# variable_supply_module_v3.net
KiCad netlist of a schematic drawn in EAGLE
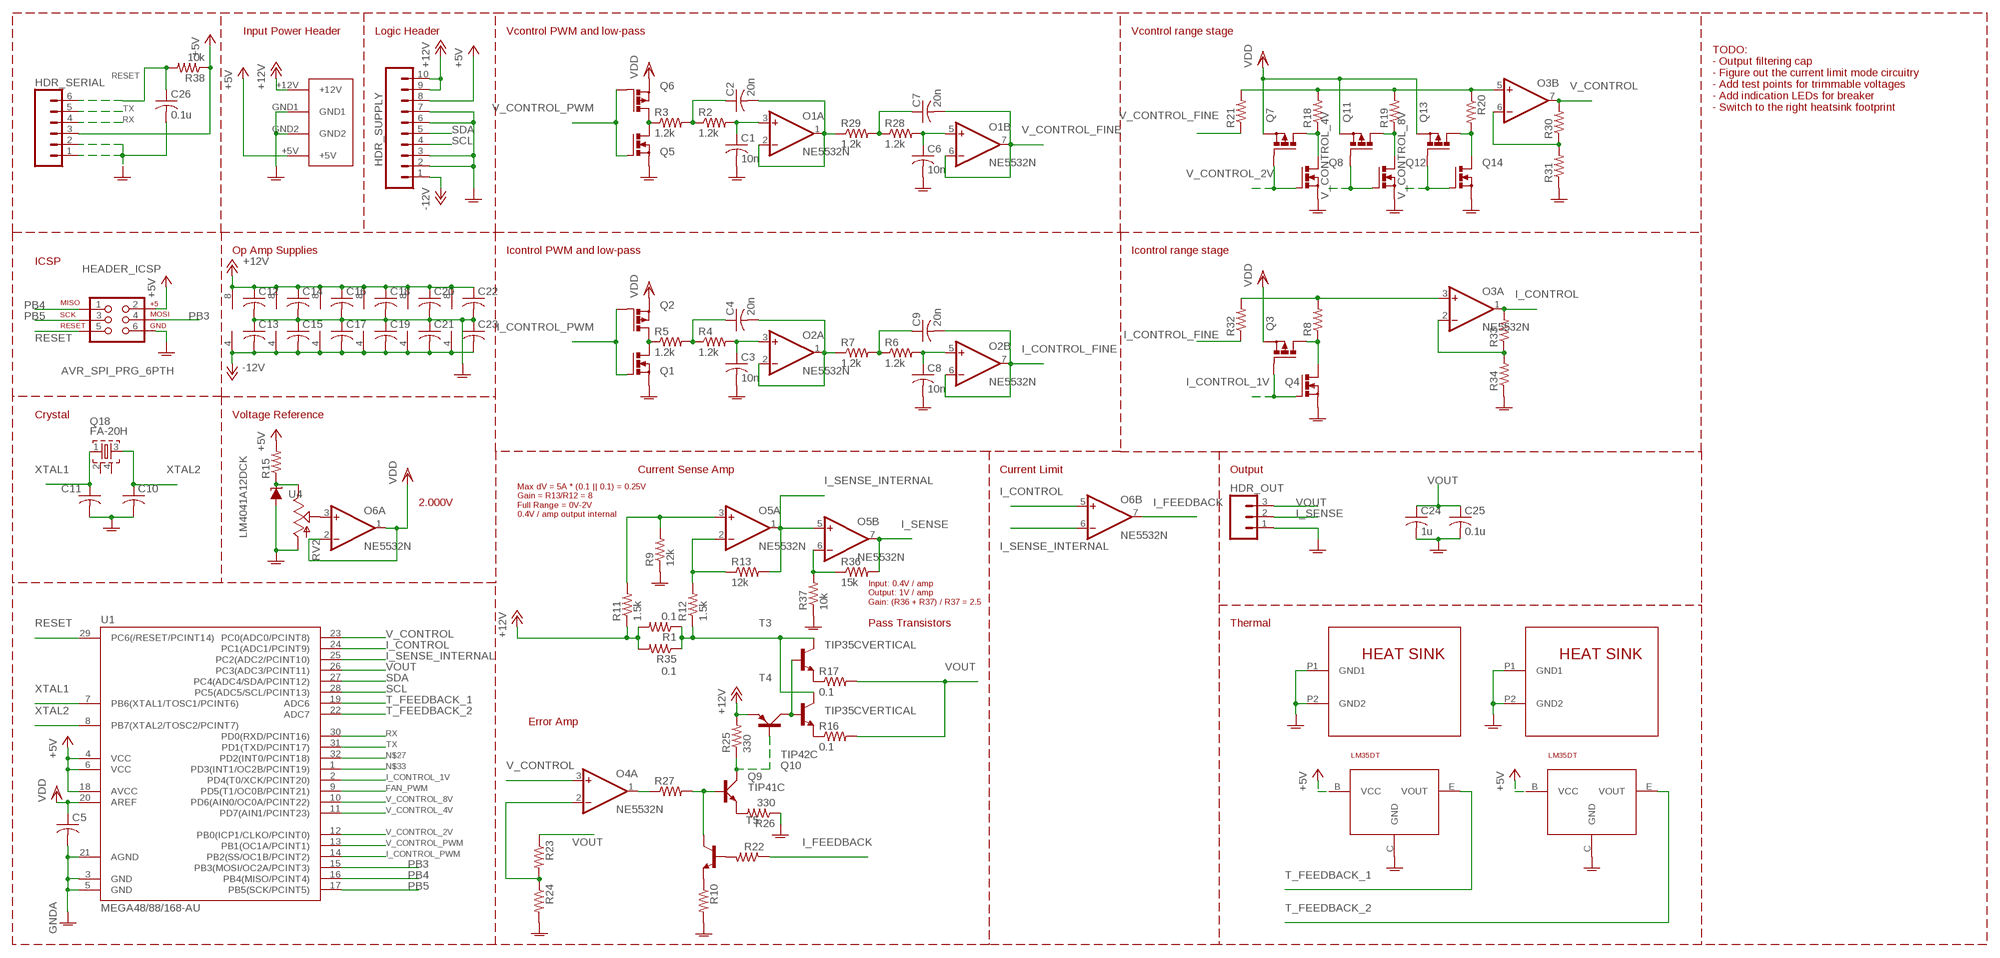
[diagram p0: schematic, sheet 1]

(export (version "E")
  (design (tool "Eeschema 10.0.6"))
  (components
    (comp (ref "C1")
      (value "10n")
      (footprint "eagle-import:C0805")
      (libsource (lib "eagle-import") (part "C-USC0805"))
    )
    (comp (ref "C2")
      (value "20n")
      (footprint "eagle-import:C0805")
      (libsource (lib "eagle-import") (part "C-USC0805"))
    )
    (comp (ref "C3")
      (value "10n")
      (footprint "eagle-import:C0805")
      (libsource (lib "eagle-import") (part "C-USC0805"))
    )
    (comp (ref "C4")
      (value "20n")
      (footprint "eagle-import:C0805")
      (libsource (lib "eagle-import") (part "C-USC0805"))
    )
    (comp (ref "C5")
      (value "C-USC0805")
      (footprint "eagle-import:C0805")
      (libsource (lib "eagle-import") (part "C-USC0805"))
    )
    (comp (ref "C6")
      (value "10n")
      (footprint "eagle-import:C0805")
      (libsource (lib "eagle-import") (part "C-USC0805"))
    )
    (comp (ref "C7")
      (value "20n")
      (footprint "eagle-import:C0805")
      (libsource (lib "eagle-import") (part "C-USC0805"))
    )
    (comp (ref "C8")
      (value "10n")
      (footprint "eagle-import:C0805")
      (libsource (lib "eagle-import") (part "C-USC0805"))
    )
    (comp (ref "C9")
      (value "20n")
      (footprint "eagle-import:C0805")
      (libsource (lib "eagle-import") (part "C-USC0805"))
    )
    (comp (ref "C10")
      (value "C-USC0805")
      (footprint "eagle-import:C0805")
      (libsource (lib "eagle-import") (part "C-USC0805"))
    )
    (comp (ref "C11")
      (value "C-USC0805")
      (footprint "eagle-import:C0805")
      (libsource (lib "eagle-import") (part "C-USC0805"))
    )
    (comp (ref "C12")
      (value "C-USC0805")
      (footprint "eagle-import:C0805")
      (libsource (lib "eagle-import") (part "C-USC0805"))
    )
    (comp (ref "C13")
      (value "C-USC0805")
      (footprint "eagle-import:C0805")
      (libsource (lib "eagle-import") (part "C-USC0805"))
    )
    (comp (ref "C14")
      (value "C-USC0805")
      (footprint "eagle-import:C0805")
      (libsource (lib "eagle-import") (part "C-USC0805"))
    )
    (comp (ref "C15")
      (value "C-USC0805")
      (footprint "eagle-import:C0805")
      (libsource (lib "eagle-import") (part "C-USC0805"))
    )
    (comp (ref "C16")
      (value "C-USC0805")
      (footprint "eagle-import:C0805")
      (libsource (lib "eagle-import") (part "C-USC0805"))
    )
    (comp (ref "C17")
      (value "C-USC0805")
      (footprint "eagle-import:C0805")
      (libsource (lib "eagle-import") (part "C-USC0805"))
    )
    (comp (ref "C18")
      (value "C-USC0805")
      (footprint "eagle-import:C0805")
      (libsource (lib "eagle-import") (part "C-USC0805"))
    )
    (comp (ref "C19")
      (value "C-USC0805")
      (footprint "eagle-import:C0805")
      (libsource (lib "eagle-import") (part "C-USC0805"))
    )
    (comp (ref "C20")
      (value "C-USC0805")
      (footprint "eagle-import:C0805")
      (libsource (lib "eagle-import") (part "C-USC0805"))
    )
    (comp (ref "C21")
      (value "C-USC0805")
      (footprint "eagle-import:C0805")
      (libsource (lib "eagle-import") (part "C-USC0805"))
    )
    (comp (ref "C22")
      (value "C-USC0805")
      (footprint "eagle-import:C0805")
      (libsource (lib "eagle-import") (part "C-USC0805"))
    )
    (comp (ref "C23")
      (value "C-USC0805")
      (footprint "eagle-import:C0805")
      (libsource (lib "eagle-import") (part "C-USC0805"))
    )
    (comp (ref "C24")
      (value "1u")
      (footprint "eagle-import:C1206")
      (libsource (lib "eagle-import") (part "C-USC1206"))
    )
    (comp (ref "C25")
      (value "0.1u")
      (footprint "eagle-import:C1206")
      (libsource (lib "eagle-import") (part "C-USC1206"))
    )
    (comp (ref "C26")
      (value "0.1u")
      (footprint "eagle-import:C0805")
      (libsource (lib "eagle-import") (part "C-USC0805"))
    )
    (comp (ref "HDR_OUT")
      (value "M03")
      (footprint "eagle-import:03P")
      (libsource (lib "eagle-import") (part "M03"))
    )
    (comp (ref "HDR_SERIAL")
      (value "M06LONGPADS")
      (footprint "eagle-import:1X06_LONGPADS")
      (libsource (lib "eagle-import") (part "M06LONGPADS"))
    )
    (comp (ref "HDR_SUPPLY")
      (value "M10")
      (footprint "eagle-import:10P")
      (libsource (lib "eagle-import") (part "M10"))
    )
    (comp (ref "HEADER_ICSP")
      (value "AVR_SPI_PRG_6PTH")
      (footprint "eagle-import:2X3")
      (libsource (lib "eagle-import") (part "AVR_SPI_PRG_6PTH"))
    )
    (comp (ref "O1")
      (value "NE5532N")
      (footprint "eagle-import:DIL08")
      (libsource (lib "eagle-import") (part "NE5532N"))
    )
    (comp (ref "O2")
      (value "NE5532N")
      (footprint "eagle-import:DIL08")
      (libsource (lib "eagle-import") (part "NE5532N"))
    )
    (comp (ref "O3")
      (value "NE5532N")
      (footprint "eagle-import:DIL08")
      (libsource (lib "eagle-import") (part "NE5532N"))
    )
    (comp (ref "O4")
      (value "NE5532N")
      (footprint "eagle-import:DIL08")
      (libsource (lib "eagle-import") (part "NE5532N"))
    )
    (comp (ref "O5")
      (value "NE5532N")
      (footprint "eagle-import:DIL08")
      (libsource (lib "eagle-import") (part "NE5532N"))
    )
    (comp (ref "O6")
      (value "NE5532N")
      (footprint "eagle-import:DIL08")
      (libsource (lib "eagle-import") (part "NE5532N"))
    )
    (comp (ref "Q1")
      (value "PMOSFET_NSOT23-GSD")
      (footprint "eagle-import:SOT23")
      (libsource (lib "eagle-import") (part "PMOSFET_NSOT23-GSD"))
    )
    (comp (ref "Q2")
      (value "PMOSFET_PSOT-23GSD")
      (footprint "eagle-import:SOT23")
      (libsource (lib "eagle-import") (part "PMOSFET_PSOT-23GSD"))
    )
    (comp (ref "Q3")
      (value "PMOSFET_PSOT-23GSD")
      (footprint "eagle-import:SOT23")
      (libsource (lib "eagle-import") (part "PMOSFET_PSOT-23GSD"))
    )
    (comp (ref "Q4")
      (value "PMOSFET_NSOT23-GSD")
      (footprint "eagle-import:SOT23")
      (libsource (lib "eagle-import") (part "PMOSFET_NSOT23-GSD"))
    )
    (comp (ref "Q5")
      (value "PMOSFET_NSOT23-GSD")
      (footprint "eagle-import:SOT23")
      (libsource (lib "eagle-import") (part "PMOSFET_NSOT23-GSD"))
    )
    (comp (ref "Q6")
      (value "PMOSFET_PSOT-23GSD")
      (footprint "eagle-import:SOT23")
      (libsource (lib "eagle-import") (part "PMOSFET_PSOT-23GSD"))
    )
    (comp (ref "Q7")
      (value "PMOSFET_PSOT-23GSD")
      (footprint "eagle-import:SOT23")
      (libsource (lib "eagle-import") (part "PMOSFET_PSOT-23GSD"))
    )
    (comp (ref "Q8")
      (value "PMOSFET_NSOT23-GSD")
      (footprint "eagle-import:SOT23")
      (libsource (lib "eagle-import") (part "PMOSFET_NSOT23-GSD"))
    )
    (comp (ref "Q9")
      (value "TIP41C")
      (footprint "eagle-import:TO220AV")
      (libsource (lib "eagle-import") (part "TIP41C"))
    )
    (comp (ref "Q10")
      (value "TIP42C")
      (footprint "eagle-import:TO220AV")
      (libsource (lib "eagle-import") (part "TIP42C"))
    )
    (comp (ref "Q11")
      (value "PMOSFET_PSOT-23GSD")
      (footprint "eagle-import:SOT23")
      (libsource (lib "eagle-import") (part "PMOSFET_PSOT-23GSD"))
    )
    (comp (ref "Q12")
      (value "PMOSFET_NSOT23-GSD")
      (footprint "eagle-import:SOT23")
      (libsource (lib "eagle-import") (part "PMOSFET_NSOT23-GSD"))
    )
    (comp (ref "Q13")
      (value "PMOSFET_PSOT-23GSD")
      (footprint "eagle-import:SOT23")
      (libsource (lib "eagle-import") (part "PMOSFET_PSOT-23GSD"))
    )
    (comp (ref "Q14")
      (value "PMOSFET_NSOT23-GSD")
      (footprint "eagle-import:SOT23")
      (libsource (lib "eagle-import") (part "PMOSFET_NSOT23-GSD"))
    )
    (comp (ref "Q18")
      (value "FA-20H")
      (footprint "eagle-import:FA-20H")
      (libsource (lib "eagle-import") (part "FA-20H"))
    )
    (comp (ref "R1")
      (value "0.1")
      (footprint "eagle-import:R2010")
      (libsource (lib "eagle-import") (part "R-US_R2010"))
    )
    (comp (ref "R2")
      (value "1.2k")
      (footprint "eagle-import:M0805")
      (libsource (lib "eagle-import") (part "R-US_M0805"))
    )
    (comp (ref "R3")
      (value "1.2k")
      (footprint "eagle-import:M0805")
      (libsource (lib "eagle-import") (part "R-US_M0805"))
    )
    (comp (ref "R4")
      (value "1.2k")
      (footprint "eagle-import:M0805")
      (libsource (lib "eagle-import") (part "R-US_M0805"))
    )
    (comp (ref "R5")
      (value "1.2k")
      (footprint "eagle-import:M0805")
      (libsource (lib "eagle-import") (part "R-US_M0805"))
    )
    (comp (ref "R6")
      (value "1.2k")
      (footprint "eagle-import:M0805")
      (libsource (lib "eagle-import") (part "R-US_M0805"))
    )
    (comp (ref "R7")
      (value "1.2k")
      (footprint "eagle-import:M0805")
      (libsource (lib "eagle-import") (part "R-US_M0805"))
    )
    (comp (ref "R8")
      (value "R-US_M0805")
      (footprint "eagle-import:M0805")
      (libsource (lib "eagle-import") (part "R-US_M0805"))
    )
    (comp (ref "R9")
      (value "12k")
      (footprint "eagle-import:M0805")
      (libsource (lib "eagle-import") (part "R-US_M0805"))
    )
    (comp (ref "R10")
      (value "R-US_M0805")
      (footprint "eagle-import:M0805")
      (libsource (lib "eagle-import") (part "R-US_M0805"))
    )
    (comp (ref "R11")
      (value "1.5k")
      (footprint "eagle-import:M0805")
      (libsource (lib "eagle-import") (part "R-US_M0805"))
    )
    (comp (ref "R12")
      (value "1.5k")
      (footprint "eagle-import:M0805")
      (libsource (lib "eagle-import") (part "R-US_M0805"))
    )
    (comp (ref "R13")
      (value "12k")
      (footprint "eagle-import:M0805")
      (libsource (lib "eagle-import") (part "R-US_M0805"))
    )
    (comp (ref "R15")
      (value "R-US_M0805")
      (footprint "eagle-import:M0805")
      (libsource (lib "eagle-import") (part "R-US_M0805"))
    )
    (comp (ref "R16")
      (value "0.1")
      (footprint "eagle-import:R2010")
      (libsource (lib "eagle-import") (part "R-US_R2010"))
    )
    (comp (ref "R17")
      (value "0.1")
      (footprint "eagle-import:R2010")
      (libsource (lib "eagle-import") (part "R-US_R2010"))
    )
    (comp (ref "R18")
      (value "R-US_M0805")
      (footprint "eagle-import:M0805")
      (libsource (lib "eagle-import") (part "R-US_M0805"))
    )
    (comp (ref "R19")
      (value "R-US_M0805")
      (footprint "eagle-import:M0805")
      (libsource (lib "eagle-import") (part "R-US_M0805"))
    )
    (comp (ref "R20")
      (value "R-US_M0805")
      (footprint "eagle-import:M0805")
      (libsource (lib "eagle-import") (part "R-US_M0805"))
    )
    (comp (ref "R21")
      (value "R-US_M0805")
      (footprint "eagle-import:M0805")
      (libsource (lib "eagle-import") (part "R-US_M0805"))
    )
    (comp (ref "R22")
      (value "R-US_M0805")
      (footprint "eagle-import:M0805")
      (libsource (lib "eagle-import") (part "R-US_M0805"))
    )
    (comp (ref "R23")
      (value "R-US_M0805")
      (footprint "eagle-import:M0805")
      (libsource (lib "eagle-import") (part "R-US_M0805"))
    )
    (comp (ref "R24")
      (value "R-US_M0805")
      (footprint "eagle-import:M0805")
      (libsource (lib "eagle-import") (part "R-US_M0805"))
    )
    (comp (ref "R25")
      (value "330")
      (footprint "eagle-import:M0805")
      (libsource (lib "eagle-import") (part "R-US_M0805"))
    )
    (comp (ref "R26")
      (value "330")
      (footprint "eagle-import:M0805")
      (libsource (lib "eagle-import") (part "R-US_M0805"))
    )
    (comp (ref "R27")
      (value "R-US_M0805")
      (footprint "eagle-import:M0805")
      (libsource (lib "eagle-import") (part "R-US_M0805"))
    )
    (comp (ref "R28")
      (value "1.2k")
      (footprint "eagle-import:M0805")
      (libsource (lib "eagle-import") (part "R-US_M0805"))
    )
    (comp (ref "R29")
      (value "1.2k")
      (footprint "eagle-import:M0805")
      (libsource (lib "eagle-import") (part "R-US_M0805"))
    )
    (comp (ref "R30")
      (value "R-US_M0805")
      (footprint "eagle-import:M0805")
      (libsource (lib "eagle-import") (part "R-US_M0805"))
    )
    (comp (ref "R31")
      (value "R-US_M0805")
      (footprint "eagle-import:M0805")
      (libsource (lib "eagle-import") (part "R-US_M0805"))
    )
    (comp (ref "R32")
      (value "R-US_M0805")
      (footprint "eagle-import:M0805")
      (libsource (lib "eagle-import") (part "R-US_M0805"))
    )
    (comp (ref "R33")
      (value "R-US_M0805")
      (footprint "eagle-import:M0805")
      (libsource (lib "eagle-import") (part "R-US_M0805"))
    )
    (comp (ref "R34")
      (value "R-US_M0805")
      (footprint "eagle-import:M0805")
      (libsource (lib "eagle-import") (part "R-US_M0805"))
    )
    (comp (ref "R35")
      (value "0.1")
      (footprint "eagle-import:R2010")
      (libsource (lib "eagle-import") (part "R-US_R2010"))
    )
    (comp (ref "R36")
      (value "15k")
      (footprint "eagle-import:M0805")
      (libsource (lib "eagle-import") (part "R-US_M0805"))
    )
    (comp (ref "R37")
      (value "10k")
      (footprint "eagle-import:M0805")
      (libsource (lib "eagle-import") (part "R-US_M0805"))
    )
    (comp (ref "R38")
      (value "10k")
      (footprint "eagle-import:M0805")
      (libsource (lib "eagle-import") (part "R-US_M0805"))
    )
    (comp (ref "RV2")
      (value "POTTRIM")
      (footprint "eagle-import:TRIM_POT")
      (libsource (lib "eagle-import") (part "POTTRIM"))
    )
    (comp (ref "T3")
      (value "TIP35CVERTICAL")
      (footprint "eagle-import:TO247")
      (libsource (lib "eagle-import") (part "TIP35CVERTICAL"))
    )
    (comp (ref "T4")
      (value "TIP35CVERTICAL")
      (footprint "eagle-import:TO247")
      (libsource (lib "eagle-import") (part "TIP35CVERTICAL"))
    )
    (comp (ref "T5")
      (value "MMBT2222ALT1-NPN-SOT23-BEC")
      (footprint "eagle-import:SOT23-BEC")
      (libsource (lib "eagle-import") (part "-NPN-SOT23-BECMMBT2222ALT1"))
    )
    (comp (ref "U$1")
      (value "MOLEX-8981")
      (footprint "eagle-import:MOLEX-8981-MALE")
      (libsource (lib "eagle-import") (part "MOLEX-8981"))
    )
    (comp (ref "U$2")
      (value "FA-T220-X")
      (footprint "eagle-import:FA-T220-X")
      (libsource (lib "eagle-import") (part "FA-T220-X"))
    )
    (comp (ref "U$3")
      (value "FA-T220-X")
      (footprint "eagle-import:FA-T220-X")
      (libsource (lib "eagle-import") (part "FA-T220-X"))
    )
    (comp (ref "U1")
      (value "MEGA48/88/168-AU")
      (footprint "eagle-import:TQFP32-08")
      (libsource (lib "eagle-import") (part "MEGA48/88/168-AU"))
    )
    (comp (ref "U2")
      (value "LM35DT")
      (footprint "eagle-import:TO220AV")
      (libsource (lib "eagle-import") (part "LM35DT"))
    )
    (comp (ref "U3")
      (value "LM35DT")
      (footprint "eagle-import:TO220AV")
      (libsource (lib "eagle-import") (part "LM35DT"))
    )
    (comp (ref "U4")
      (value "LM4041A12DCK")
      (footprint "eagle-import:DCK_R-PDSO-G5")
      (fields (field (name "MPN") "LM4041A12IDCKR"))
      (libsource (lib "eagle-import") (part "LM4041DCKA12"))
    )
  )
  (nets
    (net (code "1") (name "+5V") (class "Default")
      (node (ref "HDR_SERIAL") (pin "3") (pinfunction "3_3") (pintype "passive"))
      (node (ref "HDR_SUPPLY") (pin "8") (pinfunction "8_8") (pintype "passive"))
      (node (ref "HEADER_ICSP") (pin "2") (pinfunction "2_2") (pintype "passive"))
      (node (ref "R15") (pin "2") (pinfunction "2_2") (pintype "passive"))
      (node (ref "R38") (pin "1") (pinfunction "1_1") (pintype "passive"))
      (node (ref "U$1") (pin "+5V") (pinfunction "+5V_+5V") (pintype "bidirectional"))
      (node (ref "U1") (pin "18") (pinfunction "AVCC_18") (pintype "passive"))
      (node (ref "U1") (pin "4") (pinfunction "VCC_4") (pintype "power_in"))
      (node (ref "U1") (pin "6") (pinfunction "VCC_6") (pintype "power_in"))
      (node (ref "U2") (pin "B") (pinfunction "VCC_B") (pintype "bidirectional"))
      (node (ref "U3") (pin "B") (pinfunction "VCC_B") (pintype "bidirectional"))
    )
    (net (code "2") (name "+12V") (class "Default")
      (node (ref "C12") (pin "1") (pinfunction "1_1") (pintype "passive"))
      (node (ref "C14") (pin "1") (pinfunction "1_1") (pintype "passive"))
      (node (ref "C16") (pin "1") (pinfunction "1_1") (pintype "passive"))
      (node (ref "C18") (pin "1") (pinfunction "1_1") (pintype "passive"))
      (node (ref "C20") (pin "1") (pinfunction "1_1") (pintype "passive"))
      (node (ref "C22") (pin "1") (pinfunction "1_1") (pintype "passive"))
      (node (ref "HDR_SUPPLY") (pin "10") (pinfunction "10_10") (pintype "passive"))
      (node (ref "HDR_SUPPLY") (pin "9") (pinfunction "9_9") (pintype "passive"))
      (node (ref "O1") (pin "8") (pinfunction "V+_8") (pintype "power_in"))
      (node (ref "O2") (pin "8") (pinfunction "V+_8") (pintype "power_in"))
      (node (ref "O3") (pin "8") (pinfunction "V+_8") (pintype "power_in"))
      (node (ref "O4") (pin "8") (pinfunction "V+_8") (pintype "power_in"))
      (node (ref "O5") (pin "8") (pinfunction "V+_8") (pintype "power_in"))
      (node (ref "O6") (pin "8") (pinfunction "V+_8") (pintype "power_in"))
      (node (ref "Q10") (pin "E") (pinfunction "E_E") (pintype "passive"))
      (node (ref "R1") (pin "2") (pinfunction "2_2") (pintype "passive"))
      (node (ref "R11") (pin "1") (pinfunction "1_1") (pintype "passive"))
      (node (ref "R25") (pin "2") (pinfunction "2_2") (pintype "passive"))
      (node (ref "R35") (pin "2") (pinfunction "2_2") (pintype "passive"))
      (node (ref "U$1") (pin "+12V") (pinfunction "+12V_+12V") (pintype "bidirectional"))
    )
    (net (code "3") (name "-12V") (class "Default")
      (node (ref "C13") (pin "2") (pinfunction "2_2") (pintype "passive"))
      (node (ref "C15") (pin "2") (pinfunction "2_2") (pintype "passive"))
      (node (ref "C17") (pin "2") (pinfunction "2_2") (pintype "passive"))
      (node (ref "C19") (pin "2") (pinfunction "2_2") (pintype "passive"))
      (node (ref "C21") (pin "2") (pinfunction "2_2") (pintype "passive"))
      (node (ref "C23") (pin "2") (pinfunction "2_2") (pintype "passive"))
      (node (ref "HDR_SUPPLY") (pin "1") (pinfunction "1_1") (pintype "passive"))
      (node (ref "O1") (pin "4") (pinfunction "V-_4") (pintype "power_in"))
      (node (ref "O2") (pin "4") (pinfunction "V-_4") (pintype "power_in"))
      (node (ref "O3") (pin "4") (pinfunction "V-_4") (pintype "power_in"))
      (node (ref "O4") (pin "4") (pinfunction "V-_4") (pintype "power_in"))
      (node (ref "O5") (pin "4") (pinfunction "V-_4") (pintype "power_in"))
      (node (ref "O6") (pin "4") (pinfunction "V-_4") (pintype "power_in"))
    )
    (net (code "4") (name "/FAN_PWM") (class "Default")
      (node (ref "U1") (pin "9") (pinfunction "PD5(T1/OC0B/PCINT21)_9") (pintype "bidirectional"))
    )
    (net (code "5") (name "/I_CONTROL") (class "Default")
      (node (ref "O3") (pin "1") (pinfunction "OUT_1") (pintype "output"))
      (node (ref "O6") (pin "5") (pinfunction "+IN_5") (pintype "input"))
      (node (ref "R33") (pin "2") (pinfunction "2_2") (pintype "passive"))
      (node (ref "U1") (pin "24") (pinfunction "PC1(ADC1/PCINT9)_24") (pintype "bidirectional"))
    )
    (net (code "6") (name "/I_CONTROL_1V") (class "Default")
      (node (ref "Q3") (pin "1") (pinfunction "G_1") (pintype "passive"))
      (node (ref "Q4") (pin "1") (pinfunction "G_1") (pintype "passive"))
      (node (ref "U1") (pin "2") (pinfunction "PD4(T0/XCK/PCINT20)_2") (pintype "bidirectional"))
    )
    (net (code "7") (name "/I_CONTROL_FINE") (class "Default")
      (node (ref "C9") (pin "2") (pinfunction "2_2") (pintype "passive"))
      (node (ref "O2") (pin "6") (pinfunction "-IN_6") (pintype "input"))
      (node (ref "O2") (pin "7") (pinfunction "OUT_7") (pintype "output"))
      (node (ref "R32") (pin "1") (pinfunction "1_1") (pintype "passive"))
    )
    (net (code "8") (name "/I_CONTROL_PWM") (class "Default")
      (node (ref "Q1") (pin "1") (pinfunction "G_1") (pintype "passive"))
      (node (ref "Q2") (pin "1") (pinfunction "G_1") (pintype "passive"))
      (node (ref "U1") (pin "14") (pinfunction "PB2(SS/OC1B/PCINT2)_14") (pintype "bidirectional"))
    )
    (net (code "9") (name "/I_FEEDBACK") (class "Default")
      (node (ref "O6") (pin "7") (pinfunction "OUT_7") (pintype "output"))
      (node (ref "R22") (pin "1") (pinfunction "1_1") (pintype "passive"))
    )
    (net (code "10") (name "/I_SENSE") (class "Default")
      (node (ref "HDR_OUT") (pin "2") (pinfunction "2_2") (pintype "passive"))
      (node (ref "O5") (pin "7") (pinfunction "OUT_7") (pintype "output"))
      (node (ref "R36") (pin "2") (pinfunction "2_2") (pintype "passive"))
    )
    (net (code "11") (name "/I_SENSE_INTERNAL") (class "Default")
      (node (ref "O5") (pin "1") (pinfunction "OUT_1") (pintype "output"))
      (node (ref "O5") (pin "5") (pinfunction "+IN_5") (pintype "input"))
      (node (ref "O6") (pin "6") (pinfunction "-IN_6") (pintype "input"))
      (node (ref "R13") (pin "2") (pinfunction "2_2") (pintype "passive"))
      (node (ref "U1") (pin "25") (pinfunction "PC2(ADC2/PCINT10)_25") (pintype "bidirectional"))
    )
    (net (code "12") (name "/N$27") (class "Default")
      (node (ref "U1") (pin "32") (pinfunction "PD2(INT0/PCINT18)_32") (pintype "bidirectional"))
    )
    (net (code "13") (name "/N$33") (class "Default")
      (node (ref "U1") (pin "1") (pinfunction "PD3(INT1/OC2B/PCINT19)_1") (pintype "bidirectional"))
    )
    (net (code "14") (name "/PB3") (class "Default")
      (node (ref "HEADER_ICSP") (pin "4") (pinfunction "4_4") (pintype "passive"))
      (node (ref "U1") (pin "15") (pinfunction "PB3(MOSI/OC2A/PCINT3)_15") (pintype "bidirectional"))
    )
    (net (code "15") (name "/PB4") (class "Default")
      (node (ref "HEADER_ICSP") (pin "1") (pinfunction "1_1") (pintype "passive"))
      (node (ref "U1") (pin "16") (pinfunction "PB4(MISO/PCINT4)_16") (pintype "bidirectional"))
    )
    (net (code "16") (name "/PB5") (class "Default")
      (node (ref "HEADER_ICSP") (pin "3") (pinfunction "3_3") (pintype "passive"))
      (node (ref "U1") (pin "17") (pinfunction "PB5(SCK/PCINT5)_17") (pintype "bidirectional"))
    )
    (net (code "17") (name "/RESET") (class "Default")
      (node (ref "C26") (pin "1") (pinfunction "1_1") (pintype "passive"))
      (node (ref "HDR_SERIAL") (pin "6") (pinfunction "6_6") (pintype "passive"))
      (node (ref "HEADER_ICSP") (pin "5") (pinfunction "5_5") (pintype "passive"))
      (node (ref "R38") (pin "2") (pinfunction "2_2") (pintype "passive"))
      (node (ref "U1") (pin "29") (pinfunction "PC6(/RESET/PCINT14)_29") (pintype "bidirectional"))
    )
    (net (code "18") (name "/RX") (class "Default")
      (node (ref "HDR_SERIAL") (pin "4") (pinfunction "4_4") (pintype "passive"))
      (node (ref "U1") (pin "30") (pinfunction "PD0(RXD/PCINT16)_30") (pintype "bidirectional"))
    )
    (net (code "19") (name "/SCL") (class "Default")
      (node (ref "HDR_SUPPLY") (pin "4") (pinfunction "4_4") (pintype "passive"))
      (node (ref "U1") (pin "28") (pinfunction "PC5(ADC5/SCL/PCINT13)_28") (pintype "bidirectional"))
    )
    (net (code "20") (name "/SDA") (class "Default")
      (node (ref "HDR_SUPPLY") (pin "5") (pinfunction "5_5") (pintype "passive"))
      (node (ref "U1") (pin "27") (pinfunction "PC4(ADC4/SDA/PCINT12)_27") (pintype "bidirectional"))
    )
    (net (code "21") (name "/TX") (class "Default")
      (node (ref "HDR_SERIAL") (pin "5") (pinfunction "5_5") (pintype "passive"))
      (node (ref "U1") (pin "31") (pinfunction "PD1(TXD/PCINT17)_31") (pintype "bidirectional"))
    )
    (net (code "22") (name "/T_FEEDBACK_1") (class "Default")
      (node (ref "U1") (pin "19") (pinfunction "ADC6_19") (pintype "passive"))
      (node (ref "U2") (pin "E") (pinfunction "VOUT_E") (pintype "bidirectional"))
    )
    (net (code "23") (name "/T_FEEDBACK_2") (class "Default")
      (node (ref "U1") (pin "22") (pinfunction "ADC7_22") (pintype "passive"))
      (node (ref "U3") (pin "E") (pinfunction "VOUT_E") (pintype "bidirectional"))
    )
    (net (code "24") (name "/VOUT") (class "Default")
      (node (ref "C24") (pin "1") (pinfunction "1_1") (pintype "passive"))
      (node (ref "C25") (pin "1") (pinfunction "1_1") (pintype "passive"))
      (node (ref "HDR_OUT") (pin "3") (pinfunction "3_3") (pintype "passive"))
      (node (ref "R16") (pin "2") (pinfunction "2_2") (pintype "passive"))
      (node (ref "R17") (pin "2") (pinfunction "2_2") (pintype "passive"))
      (node (ref "R23") (pin "1") (pinfunction "1_1") (pintype "passive"))
      (node (ref "U1") (pin "26") (pinfunction "PC3(ADC3/PCINT11)_26") (pintype "bidirectional"))
    )
    (net (code "25") (name "/V_CONTROL") (class "Default")
      (node (ref "O3") (pin "7") (pinfunction "OUT_7") (pintype "output"))
      (node (ref "O4") (pin "3") (pinfunction "+IN_3") (pintype "input"))
      (node (ref "R30") (pin "2") (pinfunction "2_2") (pintype "passive"))
      (node (ref "U1") (pin "23") (pinfunction "PC0(ADC0/PCINT8)_23") (pintype "bidirectional"))
    )
    (net (code "26") (name "/V_CONTROL_2V") (class "Default")
      (node (ref "Q7") (pin "1") (pinfunction "G_1") (pintype "passive"))
      (node (ref "Q8") (pin "1") (pinfunction "G_1") (pintype "passive"))
      (node (ref "U1") (pin "12") (pinfunction "PB0(ICP1/CLKO/PCINT0)_12") (pintype "bidirectional"))
    )
    (net (code "27") (name "/V_CONTROL_4V") (class "Default")
      (node (ref "Q11") (pin "1") (pinfunction "G_1") (pintype "passive"))
      (node (ref "Q12") (pin "1") (pinfunction "G_1") (pintype "passive"))
      (node (ref "U1") (pin "11") (pinfunction "PD7(AIN1/PCINT23)_11") (pintype "bidirectional"))
    )
    (net (code "28") (name "/V_CONTROL_8V") (class "Default")
      (node (ref "Q13") (pin "1") (pinfunction "G_1") (pintype "passive"))
      (node (ref "Q14") (pin "1") (pinfunction "G_1") (pintype "passive"))
      (node (ref "U1") (pin "10") (pinfunction "PD6(AIN0/OC0A/PCINT22)_10") (pintype "bidirectional"))
    )
    (net (code "29") (name "/V_CONTROL_FINE") (class "Default")
      (node (ref "C7") (pin "2") (pinfunction "2_2") (pintype "passive"))
      (node (ref "O1") (pin "6") (pinfunction "-IN_6") (pintype "input"))
      (node (ref "O1") (pin "7") (pinfunction "OUT_7") (pintype "output"))
      (node (ref "R21") (pin "1") (pinfunction "1_1") (pintype "passive"))
    )
    (net (code "30") (name "/V_CONTROL_PWM") (class "Default")
      (node (ref "Q5") (pin "1") (pinfunction "G_1") (pintype "passive"))
      (node (ref "Q6") (pin "1") (pinfunction "G_1") (pintype "passive"))
      (node (ref "U1") (pin "13") (pinfunction "PB1(OC1A/PCINT1)_13") (pintype "bidirectional"))
    )
    (net (code "31") (name "/XTAL1") (class "Default")
      (node (ref "C11") (pin "1") (pinfunction "1_1") (pintype "passive"))
      (node (ref "Q18") (pin "1") (pinfunction "1_1") (pintype "passive"))
      (node (ref "U1") (pin "7") (pinfunction "PB6(XTAL1/TOSC1/PCINT6)_7") (pintype "bidirectional"))
    )
    (net (code "32") (name "/XTAL2") (class "Default")
      (node (ref "C10") (pin "1") (pinfunction "1_1") (pintype "passive"))
      (node (ref "Q18") (pin "3") (pinfunction "3_3") (pintype "passive"))
      (node (ref "U1") (pin "8") (pinfunction "PB7(XTAL2/TOSC2/PCINT7)_8") (pintype "bidirectional"))
    )
    (net (code "33") (name "GNDA") (class "Default")
      (node (ref "C1") (pin "2") (pinfunction "2_2") (pintype "passive"))
      (node (ref "C10") (pin "2") (pinfunction "2_2") (pintype "passive"))
      (node (ref "C11") (pin "2") (pinfunction "2_2") (pintype "passive"))
      (node (ref "C12") (pin "2") (pinfunction "2_2") (pintype "passive"))
      (node (ref "C13") (pin "1") (pinfunction "1_1") (pintype "passive"))
      (node (ref "C14") (pin "2") (pinfunction "2_2") (pintype "passive"))
      (node (ref "C15") (pin "1") (pinfunction "1_1") (pintype "passive"))
      (node (ref "C16") (pin "2") (pinfunction "2_2") (pintype "passive"))
      (node (ref "C17") (pin "1") (pinfunction "1_1") (pintype "passive"))
      (node (ref "C18") (pin "2") (pinfunction "2_2") (pintype "passive"))
      (node (ref "C19") (pin "1") (pinfunction "1_1") (pintype "passive"))
      (node (ref "C20") (pin "2") (pinfunction "2_2") (pintype "passive"))
      (node (ref "C21") (pin "1") (pinfunction "1_1") (pintype "passive"))
      (node (ref "C22") (pin "2") (pinfunction "2_2") (pintype "passive"))
      (node (ref "C23") (pin "1") (pinfunction "1_1") (pintype "passive"))
      (node (ref "C24") (pin "2") (pinfunction "2_2") (pintype "passive"))
      (node (ref "C25") (pin "2") (pinfunction "2_2") (pintype "passive"))
      (node (ref "C26") (pin "2") (pinfunction "2_2") (pintype "passive"))
      (node (ref "C3") (pin "2") (pinfunction "2_2") (pintype "passive"))
      (node (ref "C5") (pin "2") (pinfunction "2_2") (pintype "passive"))
      (node (ref "C6") (pin "2") (pinfunction "2_2") (pintype "passive"))
      (node (ref "C8") (pin "2") (pinfunction "2_2") (pintype "passive"))
      (node (ref "HDR_OUT") (pin "1") (pinfunction "1_1") (pintype "passive"))
      (node (ref "HDR_SERIAL") (pin "1") (pinfunction "1_1") (pintype "passive"))
      (node (ref "HDR_SERIAL") (pin "2") (pinfunction "2_2") (pintype "passive"))
      (node (ref "HDR_SUPPLY") (pin "2") (pinfunction "2_2") (pintype "passive"))
      (node (ref "HDR_SUPPLY") (pin "3") (pinfunction "3_3") (pintype "passive"))
      (node (ref "HDR_SUPPLY") (pin "6") (pinfunction "6_6") (pintype "passive"))
      (node (ref "HDR_SUPPLY") (pin "7") (pinfunction "7_7") (pintype "passive"))
      (node (ref "HEADER_ICSP") (pin "6") (pinfunction "6_6") (pintype "passive"))
      (node (ref "Q1") (pin "2") (pinfunction "S_2") (pintype "passive"))
      (node (ref "Q12") (pin "2") (pinfunction "S_2") (pintype "passive"))
      (node (ref "Q14") (pin "2") (pinfunction "S_2") (pintype "passive"))
      (node (ref "Q4") (pin "2") (pinfunction "S_2") (pintype "passive"))
      (node (ref "Q5") (pin "2") (pinfunction "S_2") (pintype "passive"))
      (node (ref "Q8") (pin "2") (pinfunction "S_2") (pintype "passive"))
      (node (ref "R10") (pin "2") (pinfunction "2_2") (pintype "passive"))
      (node (ref "R24") (pin "2") (pinfunction "2_2") (pintype "passive"))
      (node (ref "R26") (pin "1") (pinfunction "1_1") (pintype "passive"))
      (node (ref "R31") (pin "1") (pinfunction "1_1") (pintype "passive"))
      (node (ref "R34") (pin "1") (pinfunction "1_1") (pintype "passive"))
      (node (ref "R37") (pin "1") (pinfunction "1_1") (pintype "passive"))
      (node (ref "R9") (pin "1") (pinfunction "1_1") (pintype "passive"))
      (node (ref "RV2") (pin "3") (pinfunction "A_3") (pintype "passive"))
      (node (ref "U$1") (pin "GND1") (pinfunction "GND1_GND1") (pintype "bidirectional"))
      (node (ref "U$1") (pin "GND2") (pinfunction "GND2_GND2") (pintype "bidirectional"))
      (node (ref "U$2") (pin "P1") (pinfunction "GND1_P1") (pintype "bidirectional"))
      (node (ref "U$2") (pin "P2") (pinfunction "GND2_P2") (pintype "bidirectional"))
      (node (ref "U$3") (pin "P1") (pinfunction "GND1_P1") (pintype "bidirectional"))
      (node (ref "U$3") (pin "P2") (pinfunction "GND2_P2") (pintype "bidirectional"))
      (node (ref "U1") (pin "21") (pinfunction "AGND_21") (pintype "power_in"))
      (node (ref "U1") (pin "3") (pinfunction "GND_3") (pintype "power_in"))
      (node (ref "U1") (pin "5") (pinfunction "GND_5") (pintype "power_in"))
      (node (ref "U2") (pin "C") (pinfunction "GND_C") (pintype "bidirectional"))
      (node (ref "U3") (pin "C") (pinfunction "GND_C") (pintype "bidirectional"))
      (node (ref "U4") (pin "1") (pinfunction "A_1") (pintype "passive"))
    )
    (net (code "34") (name "Net-(C2-Pad1)") (class "Default")
      (node (ref "C2") (pin "1") (pinfunction "1_1") (pintype "passive"))
      (node (ref "R2") (pin "1") (pinfunction "1_1") (pintype "passive"))
      (node (ref "R3") (pin "2") (pinfunction "2_2") (pintype "passive"))
    )
    (net (code "35") (name "Net-(C4-Pad1)") (class "Default")
      (node (ref "C4") (pin "1") (pinfunction "1_1") (pintype "passive"))
      (node (ref "R4") (pin "1") (pinfunction "1_1") (pintype "passive"))
      (node (ref "R5") (pin "2") (pinfunction "2_2") (pintype "passive"))
    )
    (net (code "36") (name "Net-(C7-Pad1)") (class "Default")
      (node (ref "C7") (pin "1") (pinfunction "1_1") (pintype "passive"))
      (node (ref "R28") (pin "1") (pinfunction "1_1") (pintype "passive"))
      (node (ref "R29") (pin "2") (pinfunction "2_2") (pintype "passive"))
    )
    (net (code "37") (name "Net-(C9-Pad1)") (class "Default")
      (node (ref "C9") (pin "1") (pinfunction "1_1") (pintype "passive"))
      (node (ref "R6") (pin "1") (pinfunction "1_1") (pintype "passive"))
      (node (ref "R7") (pin "2") (pinfunction "2_2") (pintype "passive"))
    )
    (net (code "38") (name "Net-(O1A-+IN)") (class "Default")
      (node (ref "C1") (pin "1") (pinfunction "1_1") (pintype "passive"))
      (node (ref "O1") (pin "3") (pinfunction "+IN_3") (pintype "input"))
      (node (ref "R2") (pin "2") (pinfunction "2_2") (pintype "passive"))
    )
    (net (code "39") (name "Net-(O1A--IN)") (class "Default")
      (node (ref "C2") (pin "2") (pinfunction "2_2") (pintype "passive"))
      (node (ref "O1") (pin "1") (pinfunction "OUT_1") (pintype "output"))
      (node (ref "O1") (pin "2") (pinfunction "-IN_2") (pintype "input"))
      (node (ref "R29") (pin "1") (pinfunction "1_1") (pintype "passive"))
    )
    (net (code "40") (name "Net-(O1B-+IN)") (class "Default")
      (node (ref "C6") (pin "1") (pinfunction "1_1") (pintype "passive"))
      (node (ref "O1") (pin "5") (pinfunction "+IN_5") (pintype "input"))
      (node (ref "R28") (pin "2") (pinfunction "2_2") (pintype "passive"))
    )
    (net (code "41") (name "Net-(O2A-+IN)") (class "Default")
      (node (ref "C3") (pin "1") (pinfunction "1_1") (pintype "passive"))
      (node (ref "O2") (pin "3") (pinfunction "+IN_3") (pintype "input"))
      (node (ref "R4") (pin "2") (pinfunction "2_2") (pintype "passive"))
    )
    (net (code "42") (name "Net-(O2A--IN)") (class "Default")
      (node (ref "C4") (pin "2") (pinfunction "2_2") (pintype "passive"))
      (node (ref "O2") (pin "1") (pinfunction "OUT_1") (pintype "output"))
      (node (ref "O2") (pin "2") (pinfunction "-IN_2") (pintype "input"))
      (node (ref "R7") (pin "1") (pinfunction "1_1") (pintype "passive"))
    )
    (net (code "43") (name "Net-(O2B-+IN)") (class "Default")
      (node (ref "C8") (pin "1") (pinfunction "1_1") (pintype "passive"))
      (node (ref "O2") (pin "5") (pinfunction "+IN_5") (pintype "input"))
      (node (ref "R6") (pin "2") (pinfunction "2_2") (pintype "passive"))
    )
    (net (code "44") (name "Net-(O3A-+IN)") (class "Default")
      (node (ref "O3") (pin "3") (pinfunction "+IN_3") (pintype "input"))
      (node (ref "R32") (pin "2") (pinfunction "2_2") (pintype "passive"))
      (node (ref "R8") (pin "2") (pinfunction "2_2") (pintype "passive"))
    )
    (net (code "45") (name "Net-(O3A--IN)") (class "Default")
      (node (ref "O3") (pin "2") (pinfunction "-IN_2") (pintype "input"))
      (node (ref "R33") (pin "1") (pinfunction "1_1") (pintype "passive"))
      (node (ref "R34") (pin "2") (pinfunction "2_2") (pintype "passive"))
    )
    (net (code "46") (name "Net-(O3B-+IN)") (class "Default")
      (node (ref "O3") (pin "5") (pinfunction "+IN_5") (pintype "input"))
      (node (ref "R18") (pin "2") (pinfunction "2_2") (pintype "passive"))
      (node (ref "R19") (pin "2") (pinfunction "2_2") (pintype "passive"))
      (node (ref "R20") (pin "1") (pinfunction "1_1") (pintype "passive"))
      (node (ref "R21") (pin "2") (pinfunction "2_2") (pintype "passive"))
    )
    (net (code "47") (name "Net-(O3B--IN)") (class "Default")
      (node (ref "O3") (pin "6") (pinfunction "-IN_6") (pintype "input"))
      (node (ref "R30") (pin "1") (pinfunction "1_1") (pintype "passive"))
      (node (ref "R31") (pin "2") (pinfunction "2_2") (pintype "passive"))
    )
    (net (code "48") (name "Net-(O4A--IN)") (class "Default")
      (node (ref "O4") (pin "2") (pinfunction "-IN_2") (pintype "input"))
      (node (ref "R23") (pin "2") (pinfunction "2_2") (pintype "passive"))
      (node (ref "R24") (pin "1") (pinfunction "1_1") (pintype "passive"))
    )
    (net (code "49") (name "Net-(O4A-OUT)") (class "Default")
      (node (ref "O4") (pin "1") (pinfunction "OUT_1") (pintype "output"))
      (node (ref "R27") (pin "1") (pinfunction "1_1") (pintype "passive"))
    )
    (net (code "50") (name "Net-(O5A-+IN)") (class "Default")
      (node (ref "O5") (pin "3") (pinfunction "+IN_3") (pintype "input"))
      (node (ref "R11") (pin "2") (pinfunction "2_2") (pintype "passive"))
      (node (ref "R9") (pin "2") (pinfunction "2_2") (pintype "passive"))
    )
    (net (code "51") (name "Net-(O5A--IN)") (class "Default")
      (node (ref "O5") (pin "2") (pinfunction "-IN_2") (pintype "input"))
      (node (ref "R12") (pin "2") (pinfunction "2_2") (pintype "passive"))
      (node (ref "R13") (pin "1") (pinfunction "1_1") (pintype "passive"))
    )
    (net (code "52") (name "Net-(O5B--IN)") (class "Default")
      (node (ref "O5") (pin "6") (pinfunction "-IN_6") (pintype "input"))
      (node (ref "R36") (pin "1") (pinfunction "1_1") (pintype "passive"))
      (node (ref "R37") (pin "2") (pinfunction "2_2") (pintype "passive"))
    )
    (net (code "53") (name "Net-(O6A-+IN)") (class "Default")
      (node (ref "O6") (pin "3") (pinfunction "+IN_3") (pintype "input"))
      (node (ref "RV2") (pin "1") (pinfunction "S_1") (pintype "passive"))
    )
    (net (code "54") (name "Net-(Q1-D)") (class "Default")
      (node (ref "Q1") (pin "3") (pinfunction "D_3") (pintype "passive"))
      (node (ref "Q2") (pin "3") (pinfunction "D_3") (pintype "passive"))
      (node (ref "R5") (pin "1") (pinfunction "1_1") (pintype "passive"))
    )
    (net (code "55") (name "Net-(Q3-D)") (class "Default")
      (node (ref "Q3") (pin "3") (pinfunction "D_3") (pintype "passive"))
      (node (ref "Q4") (pin "3") (pinfunction "D_3") (pintype "passive"))
      (node (ref "R8") (pin "1") (pinfunction "1_1") (pintype "passive"))
    )
    (net (code "56") (name "Net-(Q5-D)") (class "Default")
      (node (ref "Q5") (pin "3") (pinfunction "D_3") (pintype "passive"))
      (node (ref "Q6") (pin "3") (pinfunction "D_3") (pintype "passive"))
      (node (ref "R3") (pin "1") (pinfunction "1_1") (pintype "passive"))
    )
    (net (code "57") (name "Net-(Q7-D)") (class "Default")
      (node (ref "Q7") (pin "3") (pinfunction "D_3") (pintype "passive"))
      (node (ref "Q8") (pin "3") (pinfunction "D_3") (pintype "passive"))
      (node (ref "R18") (pin "1") (pinfunction "1_1") (pintype "passive"))
    )
    (net (code "58") (name "Net-(Q9-PadB)") (class "Default")
      (node (ref "Q9") (pin "B") (pinfunction "B_B") (pintype "passive"))
      (node (ref "R27") (pin "2") (pinfunction "2_2") (pintype "passive"))
      (node (ref "T5") (pin "C") (pinfunction "C_C") (pintype "passive"))
    )
    (net (code "59") (name "Net-(Q9-PadE)") (class "Default")
      (node (ref "Q9") (pin "E") (pinfunction "E_E") (pintype "passive"))
      (node (ref "R26") (pin "2") (pinfunction "2_2") (pintype "passive"))
    )
    (net (code "60") (name "Net-(Q10-PadB)") (class "Default")
      (node (ref "Q10") (pin "B") (pinfunction "B_B") (pintype "passive"))
      (node (ref "Q9") (pin "C") (pinfunction "C_C") (pintype "passive"))
      (node (ref "R25") (pin "1") (pinfunction "1_1") (pintype "passive"))
    )
    (net (code "61") (name "Net-(Q11-D)") (class "Default")
      (node (ref "Q11") (pin "3") (pinfunction "D_3") (pintype "passive"))
      (node (ref "Q12") (pin "3") (pinfunction "D_3") (pintype "passive"))
      (node (ref "R19") (pin "1") (pinfunction "1_1") (pintype "passive"))
    )
    (net (code "62") (name "Net-(Q13-D)") (class "Default")
      (node (ref "Q13") (pin "3") (pinfunction "D_3") (pintype "passive"))
      (node (ref "Q14") (pin "3") (pinfunction "D_3") (pintype "passive"))
      (node (ref "R20") (pin "2") (pinfunction "2_2") (pintype "passive"))
    )
    (net (code "63") (name "Net-(R10-Pad1)") (class "Default")
      (node (ref "R10") (pin "1") (pinfunction "1_1") (pintype "passive"))
      (node (ref "T5") (pin "E") (pinfunction "E_E") (pintype "passive"))
    )
    (net (code "64") (name "Net-(R22-Pad2)") (class "Default")
      (node (ref "R22") (pin "2") (pinfunction "2_2") (pintype "passive"))
      (node (ref "T5") (pin "B") (pinfunction "B_B") (pintype "passive"))
    )
    (net (code "65") (name "Net-(RV2-E)") (class "Default")
      (node (ref "R15") (pin "1") (pinfunction "1_1") (pintype "passive"))
      (node (ref "RV2") (pin "2") (pinfunction "E_2") (pintype "passive"))
      (node (ref "U4") (pin "3") (pinfunction "C_3") (pintype "passive"))
    )
    (net (code "66") (name "Net-(T3-B)") (class "Default")
      (node (ref "Q10") (pin "C") (pinfunction "C_C") (pintype "passive"))
      (node (ref "T3") (pin "P1") (pinfunction "B_P1") (pintype "passive"))
      (node (ref "T4") (pin "P1") (pinfunction "B_P1") (pintype "passive"))
    )
    (net (code "67") (name "Net-(T3-C)") (class "Default")
      (node (ref "R1") (pin "1") (pinfunction "1_1") (pintype "passive"))
      (node (ref "R12") (pin "1") (pinfunction "1_1") (pintype "passive"))
      (node (ref "R35") (pin "1") (pinfunction "1_1") (pintype "passive"))
      (node (ref "T3") (pin "P2") (pinfunction "C_P2") (pintype "passive"))
      (node (ref "T4") (pin "P2") (pinfunction "C_P2") (pintype "passive"))
    )
    (net (code "68") (name "Net-(T3-E)") (class "Default")
      (node (ref "R17") (pin "1") (pinfunction "1_1") (pintype "passive"))
      (node (ref "T3") (pin "P3") (pinfunction "E_P3") (pintype "passive"))
    )
    (net (code "69") (name "Net-(T4-E)") (class "Default")
      (node (ref "R16") (pin "1") (pinfunction "1_1") (pintype "passive"))
      (node (ref "T4") (pin "P3") (pinfunction "E_P3") (pintype "passive"))
    )
    (net (code "70") (name "VDD") (class "Default")
      (node (ref "C5") (pin "1") (pinfunction "1_1") (pintype "passive"))
      (node (ref "O6") (pin "1") (pinfunction "OUT_1") (pintype "output"))
      (node (ref "O6") (pin "2") (pinfunction "-IN_2") (pintype "input"))
      (node (ref "Q11") (pin "2") (pinfunction "S_2") (pintype "passive"))
      (node (ref "Q13") (pin "2") (pinfunction "S_2") (pintype "passive"))
      (node (ref "Q2") (pin "2") (pinfunction "S_2") (pintype "passive"))
      (node (ref "Q3") (pin "2") (pinfunction "S_2") (pintype "passive"))
      (node (ref "Q6") (pin "2") (pinfunction "S_2") (pintype "passive"))
      (node (ref "Q7") (pin "2") (pinfunction "S_2") (pintype "passive"))
      (node (ref "U1") (pin "20") (pinfunction "AREF_20") (pintype "passive"))
    )
    (net (code "71") (name "unconnected-(Q18-Pad2)") (class "Default")
      (node (ref "Q18") (pin "2") (pinfunction "2_2") (pintype "passive"))
    )
    (net (code "72") (name "unconnected-(Q18-Pad4)") (class "Default")
      (node (ref "Q18") (pin "4") (pinfunction "4_4") (pintype "passive"))
    )
  )
)
